# untitled.net
KiCad netlist of a schematic drawn in EAGLE
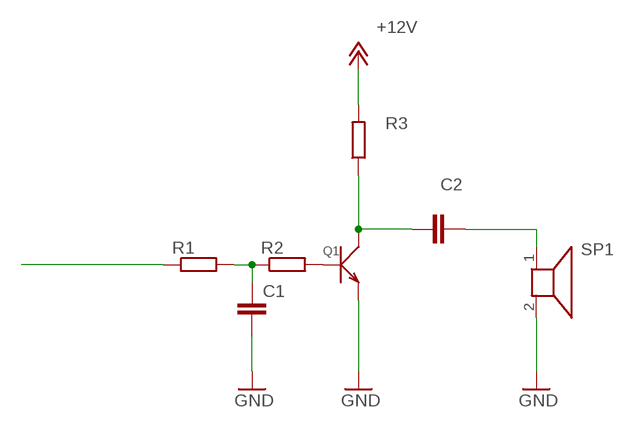
[diagram p0: schematic, sheet 1]

(export (version "E")
  (design (tool "Eeschema 10.0.6"))
  (components
    (comp (ref "C1")
      (value "C-EU025-024X044")
      (footprint "eagle-import:C025-024X044")
      (libsource (lib "eagle-import") (part "C-EU025-024X044"))
    )
    (comp (ref "C2")
      (value "C-EU025-024X044")
      (footprint "eagle-import:C025-024X044")
      (libsource (lib "eagle-import") (part "C-EU025-024X044"))
    )
    (comp (ref "Q1")
      (value "TRANSISTOR-NPN-1.27")
      (footprint "eagle-import:NPN1.27")
      (libsource (lib "eagle-import") (part "TRANSISTOR-NPN-1.27"))
    )
    (comp (ref "R1")
      (value "R-EU_0207/2V")
      (footprint "eagle-import:0207_2V")
      (libsource (lib "eagle-import") (part "R-EU_0207/2V"))
    )
    (comp (ref "R2")
      (value "R-EU_0207/2V")
      (footprint "eagle-import:0207_2V")
      (libsource (lib "eagle-import") (part "R-EU_0207/2V"))
    )
    (comp (ref "R3")
      (value "R-EU_0207/2V")
      (footprint "eagle-import:0207_2V")
      (libsource (lib "eagle-import") (part "R-EU_0207/2V"))
    )
    (comp (ref "SP1")
      (value "AL60P")
      (footprint "eagle-import:AL60P")
      (libsource (lib "eagle-import") (part "AL60P"))
    )
  )
  (nets
    (net (code "1") (name "+12V") (class "Default")
      (node (ref "R3") (pin "2") (pinfunction "2_2") (pintype "passive"))
    )
    (net (code "2") (name "GND") (class "Default")
      (node (ref "C1") (pin "2") (pinfunction "2_2") (pintype "passive"))
      (node (ref "Q1") (pin "E") (pinfunction "E_E") (pintype "passive"))
      (node (ref "SP1") (pin "2") (pinfunction "2_2") (pintype "passive"))
    )
    (net (code "3") (name "Net-(C1-Pad1)") (class "Default")
      (node (ref "C1") (pin "1") (pinfunction "1_1") (pintype "passive"))
      (node (ref "R1") (pin "2") (pinfunction "2_2") (pintype "passive"))
      (node (ref "R2") (pin "1") (pinfunction "1_1") (pintype "passive"))
    )
    (net (code "4") (name "Net-(C2-Pad1)") (class "Default")
      (node (ref "C2") (pin "1") (pinfunction "1_1") (pintype "passive"))
      (node (ref "Q1") (pin "C") (pinfunction "C_C") (pintype "passive"))
      (node (ref "R3") (pin "1") (pinfunction "1_1") (pintype "passive"))
    )
    (net (code "5") (name "Net-(C2-Pad2)") (class "Default")
      (node (ref "C2") (pin "2") (pinfunction "2_2") (pintype "passive"))
      (node (ref "SP1") (pin "1") (pinfunction "1_1") (pintype "passive"))
    )
    (net (code "6") (name "Net-(Q1-PadB)") (class "Default")
      (node (ref "Q1") (pin "B") (pinfunction "B_B") (pintype "passive"))
      (node (ref "R2") (pin "2") (pinfunction "2_2") (pintype "passive"))
    )
    (net (code "7") (name "unconnected-(R1-Pad1)") (class "Default")
      (node (ref "R1") (pin "1") (pinfunction "1_1") (pintype "passive"))
    )
  )
)
